# RS485.net
KiCad netlist of a schematic drawn in Altium Designer
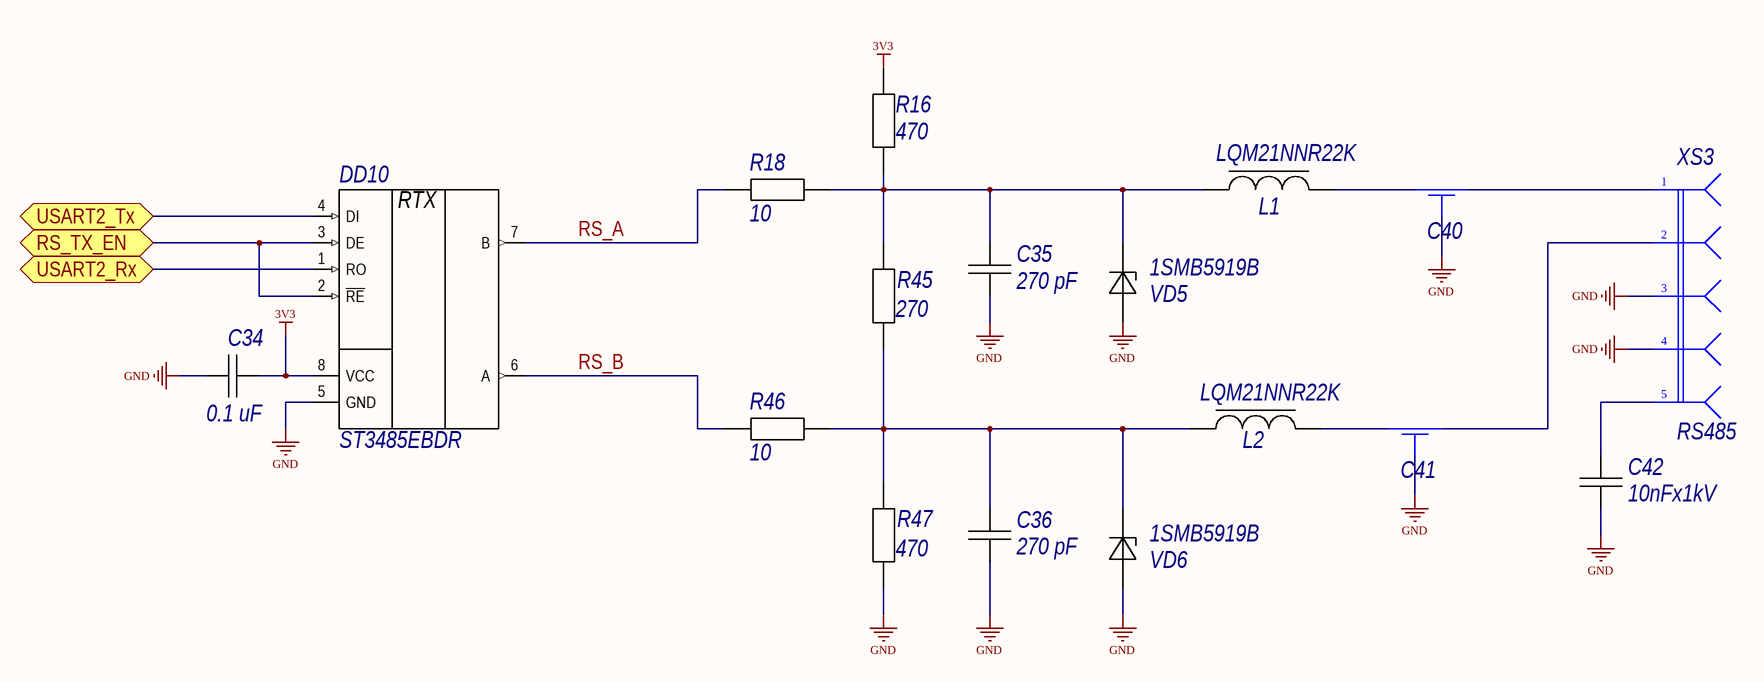
[diagram p0: RS485.SchDoc]

(export (version "E")
  (design (tool "Eeschema 10.0.6"))
  (components
    (comp (ref "C34")
      (value "0.1 uF")
      (footprint "C0805C")
      (fields (field (name "PUBLISHER") "Andrew Danich"))
      (libsource (lib "PA_control_board") (part "CAP_0805"))
    )
    (comp (ref "C35")
      (value "270 pF")
      (footprint "C0805C")
      (fields (field (name "PUBLISHER") "Andrew Danich"))
      (libsource (lib "PA_control_board") (part "CAP_0805"))
    )
    (comp (ref "C36")
      (value "270 pF")
      (footprint "C0805C")
      (fields (field (name "PUBLISHER") "Andrew Danich"))
      (libsource (lib "PA_control_board") (part "CAP_0805"))
    )
    (comp (ref "C40")
      (value "NFM3DCC222R1H3L")
      (footprint "NFM3DCC222R1H3L")
      (fields (field (name "PUBLISHER") "Andrew Danich"))
      (libsource (lib "PA_control_board") (part "NFM3DCC222R1H3L"))
    )
    (comp (ref "C41")
      (value "NFM3DCC222R1H3L")
      (footprint "NFM3DCC222R1H3L")
      (fields (field (name "PUBLISHER") "Andrew Danich"))
      (libsource (lib "PA_control_board") (part "NFM3DCC222R1H3L"))
    )
    (comp (ref "C42")
      (value "10nFx1kV")
      (footprint "C0805C")
      (fields (field (name "PUBLISHER") "Andrew Danich"))
      (libsource (lib "PA_control_board") (part "CAP_1206"))
    )
    (comp (ref "DD10")
      (value "ST3485EBDR")
      (footprint "SOIC8 (SO-8)")
      (fields (field (name "PUBLISHER") "Andrew Danich"))
      (libsource (lib "PA_control_board") (part "ST3485EBDR"))
    )
    (comp (ref "L1")
      (value "LQM21NNR22K")
      (footprint "L0805")
      (fields (field (name "PUBLISHER") "Andrew Danich"))
      (libsource (lib "PA_control_board") (part "LQM21NNR22K"))
    )
    (comp (ref "L2")
      (value "LQM21NNR22K")
      (footprint "L0805")
      (fields (field (name "PUBLISHER") "Andrew Danich"))
      (libsource (lib "PA_control_board") (part "LQM21NNR22K"))
    )
    (comp (ref "R16")
      (value "470")
      (footprint "C0805R")
      (fields (field (name "PUBLISHER") "Andrew Danich"))
      (libsource (lib "PA_control_board") (part "RES_0805"))
    )
    (comp (ref "R18")
      (value "10")
      (footprint "C0805R")
      (fields (field (name "PUBLISHER") "Andrew Danich"))
      (libsource (lib "PA_control_board") (part "RES_0805"))
    )
    (comp (ref "R45")
      (value "270")
      (footprint "C0805R")
      (fields (field (name "PUBLISHER") "Andrew Danich"))
      (libsource (lib "PA_control_board") (part "RES_0805"))
    )
    (comp (ref "R46")
      (value "10")
      (footprint "C0805R")
      (fields (field (name "PUBLISHER") "Andrew Danich"))
      (libsource (lib "PA_control_board") (part "RES_0805"))
    )
    (comp (ref "R47")
      (value "470")
      (footprint "C0805R")
      (fields (field (name "PUBLISHER") "Andrew Danich"))
      (libsource (lib "PA_control_board") (part "RES_0805"))
    )
    (comp (ref "VD5")
      (value "1SMB5919B")
      (footprint "DO214AA SMB")
      (fields (field (name "PUBLISHER") "Andrew Danich"))
      (libsource (lib "PA_control_board") (part "1SMB5919B"))
    )
    (comp (ref "VD6")
      (value "1SMB5919B")
      (footprint "DO214AA SMB")
      (fields (field (name "PUBLISHER") "Andrew Danich"))
      (libsource (lib "PA_control_board") (part "1SMB5919B"))
    )
    (comp (ref "XS3")
      (value "RS485")
      (footprint "WF-5")
      (fields (field (name "PUBLISHER") "Andrew Danich"))
      (libsource (lib "PA_control_board") (part "CONNECT_SEQ"))
    )
  )
  (nets
    (net (code "1") (name "/RS_A") (class "Default")
      (node (ref "DD10") (pin "7") (pinfunction "B_7") (pintype "output"))
      (node (ref "R18") (pin "2") (pinfunction "2_2") (pintype "passive"))
    )
    (net (code "2") (name "/RS_B") (class "Default")
      (node (ref "DD10") (pin "6") (pinfunction "A_6") (pintype "output"))
      (node (ref "R46") (pin "2") (pinfunction "2_2") (pintype "passive"))
    )
    (net (code "3") (name "/RS_TX_EN") (class "Default")
      (node (ref "DD10") (pin "2") (pinfunction "~{RE}_2") (pintype "input"))
      (node (ref "DD10") (pin "3") (pinfunction "DE_3") (pintype "input"))
    )
    (net (code "4") (name "/USART2_Rx") (class "Default")
      (node (ref "DD10") (pin "1") (pinfunction "RO_1") (pintype "input"))
    )
    (net (code "5") (name "/USART2_Tx") (class "Default")
      (node (ref "DD10") (pin "4") (pinfunction "DI_4") (pintype "input"))
    )
    (net (code "6") (name "3V3") (class "Default")
      (node (ref "C34") (pin "2") (pinfunction "2_2") (pintype "passive"))
      (node (ref "DD10") (pin "8") (pinfunction "VCC_8") (pintype "power_in"))
      (node (ref "R16") (pin "1") (pinfunction "1_1") (pintype "passive"))
    )
    (net (code "7") (name "GND") (class "Default")
      (node (ref "C34") (pin "1") (pinfunction "1_1") (pintype "passive"))
      (node (ref "C35") (pin "1") (pinfunction "1_1") (pintype "passive"))
      (node (ref "C36") (pin "1") (pinfunction "1_1") (pintype "passive"))
      (node (ref "C40") (pin "2") (pinfunction "2_2") (pintype "passive"))
      (node (ref "C41") (pin "2") (pinfunction "2_2") (pintype "passive"))
      (node (ref "C42") (pin "1") (pinfunction "1_1") (pintype "passive"))
      (node (ref "DD10") (pin "5") (pinfunction "GND_5") (pintype "passive"))
      (node (ref "R47") (pin "1") (pinfunction "1_1") (pintype "passive"))
      (node (ref "VD5") (pin "1") (pinfunction "А_1") (pintype "passive"))
      (node (ref "VD6") (pin "1") (pinfunction "А_1") (pintype "passive"))
      (node (ref "XS3") (pin "3") (pintype "passive"))
      (node (ref "XS3") (pin "4") (pintype "passive"))
    )
    (net (code "8") (name "Net-(C40-Pad1)") (class "Default")
      (node (ref "C40") (pin "1") (pinfunction "1_1") (pintype "passive"))
      (node (ref "L1") (pin "2") (pinfunction "2_2") (pintype "passive"))
    )
    (net (code "9") (name "Net-(C40-Pad3)") (class "Default")
      (node (ref "C40") (pin "3") (pinfunction "3_3") (pintype "passive"))
      (node (ref "XS3") (pin "1") (pintype "passive"))
    )
    (net (code "10") (name "Net-(C41-Pad1)") (class "Default")
      (node (ref "C41") (pin "1") (pinfunction "1_1") (pintype "passive"))
      (node (ref "L2") (pin "2") (pinfunction "2_2") (pintype "passive"))
    )
    (net (code "11") (name "Net-(C41-Pad3)") (class "Default")
      (node (ref "C41") (pin "3") (pinfunction "3_3") (pintype "passive"))
      (node (ref "XS3") (pin "2") (pintype "passive"))
    )
    (net (code "12") (name "Net-(C42-Pad2)") (class "Default")
      (node (ref "C42") (pin "2") (pinfunction "2_2") (pintype "passive"))
      (node (ref "XS3") (pin "5") (pintype "passive"))
    )
    (net (code "13") (name "Net-(VD5-К)") (class "Default")
      (node (ref "C35") (pin "2") (pinfunction "2_2") (pintype "passive"))
      (node (ref "L1") (pin "1") (pinfunction "1_1") (pintype "passive"))
      (node (ref "R16") (pin "2") (pinfunction "2_2") (pintype "passive"))
      (node (ref "R18") (pin "1") (pinfunction "1_1") (pintype "passive"))
      (node (ref "R45") (pin "2") (pinfunction "2_2") (pintype "passive"))
      (node (ref "VD5") (pin "2") (pinfunction "К_2") (pintype "passive"))
    )
    (net (code "14") (name "Net-(VD6-К)") (class "Default")
      (node (ref "C36") (pin "2") (pinfunction "2_2") (pintype "passive"))
      (node (ref "L2") (pin "1") (pinfunction "1_1") (pintype "passive"))
      (node (ref "R45") (pin "1") (pinfunction "1_1") (pintype "passive"))
      (node (ref "R46") (pin "1") (pinfunction "1_1") (pintype "passive"))
      (node (ref "R47") (pin "2") (pinfunction "2_2") (pintype "passive"))
      (node (ref "VD6") (pin "2") (pinfunction "К_2") (pintype "passive"))
    )
  )
)
